# MCU_EM.net
KiCad netlist of a schematic drawn in Altium Designer
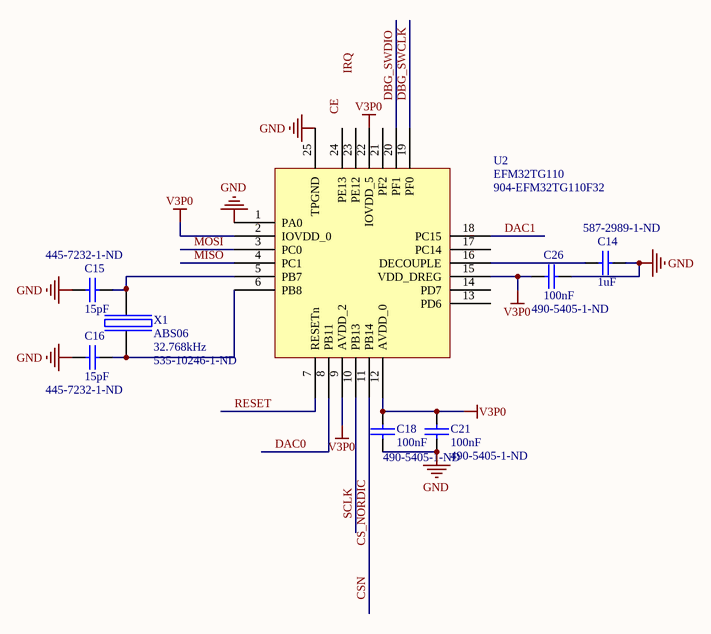
[diagram p0: MCU_EM.SchDoc]

(export (version "E")
  (design (tool "Eeschema 10.0.6"))
  (components
    (comp (ref "C14")
      (value "1uF")
      (footprint "0402s")
      (description "Capacitor")
      (fields
        (field (name "SUPPLIER PART NUMBER 1") "587-2989-1-ND")
        (field (name "MANUFACTURER") "Taiyo Yuden")
        (field (name "MANUFACTURER PART NUMBER") "AMK063ABJ105MP-F")
      )
      (libsource (lib "nRF24LE1F16Q24") (part "Cap"))
    )
    (comp (ref "C15")
      (value "15pF")
      (footprint "0201")
      (description "Capacitor")
      (fields
        (field (name "SUPPLIER PART NUMBER 1") "445-7232-1-ND")
        (field (name "MANUFACTURER") "TDK Corporation")
        (field (name "MANUFACTURER PART NUMBER") "C0603C0G1E150G")
      )
      (libsource (lib "nRF24LE1F16Q24") (part "Cap"))
    )
    (comp (ref "C16")
      (value "15pF")
      (footprint "0201")
      (description "Capacitor")
      (fields
        (field (name "SUPPLIER PART NUMBER 1") "445-7232-1-ND")
        (field (name "MANUFACTURER") "TDK Corporation")
        (field (name "MANUFACTURER PART NUMBER") "C0603C0G1E150G")
      )
      (libsource (lib "nRF24LE1F16Q24") (part "Cap"))
    )
    (comp (ref "C18")
      (value "100nF")
      (footprint "0201")
      (description "Capacitor")
      (fields
        (field (name "SUPPLIER PART NUMBER 1") "490-5405-1-ND")
        (field (name "MANUFACTURER") "Murata Electronics North America")
        (field (name "MANUFACTURER PART NUMBER") "GRM033R61A104ME15D")
      )
      (libsource (lib "nRF24LE1F16Q24") (part "Cap"))
    )
    (comp (ref "C21")
      (value "100nF")
      (footprint "0201")
      (description "Capacitor")
      (fields
        (field (name "SUPPLIER PART NUMBER 1") "490-5405-1-ND")
        (field (name "MANUFACTURER") "Murata Electronics North America")
        (field (name "MANUFACTURER PART NUMBER") "GRM033R61A104ME15D")
      )
      (libsource (lib "nRF24LE1F16Q24") (part "Cap"))
    )
    (comp (ref "C26")
      (value "100nF")
      (footprint "0402s")
      (description "Capacitor")
      (fields
        (field (name "SUPPLIER PART NUMBER 1") "490-5405-1-ND")
        (field (name "MANUFACTURER") "Murata Electronics North America")
        (field (name "MANUFACTURER PART NUMBER") "GRM033R61A104ME15D")
      )
      (libsource (lib "nRF24LE1F16Q24") (part "Cap"))
    )
    (comp (ref "U2")
      (value "EFM32TG110")
      (footprint "QFN24_EM")
      (description "Microcontrollers (MCU) 32KB Flash 4KB RAM")
      (fields
        (field (name "MANUFACTURER") "Energy Micro")
        (field (name "SUPPLIER PART NUMBER 1") "904-EFM32TG110F32")
      )
      (libsource (lib "custom") (part "EFM32TG110"))
    )
    (comp (ref "X1")
      (value "ABS06")
      (footprint "ABS06")
      (description "CRYSTAL 32.768 KHZ 9.0 PF SMD")
      (fields
        (field (name "MANUFACTURER") "Abracon Corporation")
        (field (name "MANUFACTURER PART NUMBER") "ABS06-32.768KHZ-9-T")
        (field (name "FREQUENCY") "32.768kHz")
        (field (name "SUPPLIER PART NUMBER 1") "535-10246-1-ND")
      )
      (libsource (lib "custom") (part "ABS06"))
    )
  )
  (nets
    (net (code "2") (name "/CSN") (class "Default")
      (node (ref "U2") (pin "11") (pinfunction "PB14_11") (pintype "passive"))
    )
    (net (code "3") (name "/DAC0") (class "Default")
      (node (ref "U2") (pin "8") (pinfunction "PB11_8") (pintype "passive"))
    )
    (net (code "4") (name "/DAC1") (class "Default")
      (node (ref "U2") (pin "18") (pinfunction "PC15_18") (pintype "passive"))
    )
    (net (code "5") (name "/DBG_SWCLK") (class "Default")
      (node (ref "U2") (pin "19") (pinfunction "PF0_19") (pintype "passive"))
    )
    (net (code "6") (name "/DBG_SWDIO") (class "Default")
      (node (ref "U2") (pin "20") (pinfunction "PF1_20") (pintype "passive"))
    )
    (net (code "8") (name "/MISO") (class "Default")
      (node (ref "U2") (pin "4") (pinfunction "PC1_4") (pintype "passive"))
    )
    (net (code "9") (name "/MOSI") (class "Default")
      (node (ref "U2") (pin "3") (pinfunction "PC0_3") (pintype "passive"))
    )
    (net (code "10") (name "/RESET") (class "Default")
      (node (ref "U2") (pin "7") (pinfunction "RESETn_7") (pintype "passive"))
    )
    (net (code "11") (name "/SCLK") (class "Default")
      (node (ref "U2") (pin "10") (pinfunction "PB13_10") (pintype "passive"))
    )
    (net (code "12") (name "GND") (class "Default")
      (node (ref "C14") (pin "1") (pintype "passive"))
      (node (ref "C15") (pin "1") (pintype "passive"))
      (node (ref "C16") (pin "2") (pintype "passive"))
      (node (ref "C18") (pin "2") (pintype "passive"))
      (node (ref "C21") (pin "2") (pintype "passive"))
      (node (ref "C26") (pin "2") (pintype "passive"))
      (node (ref "U2") (pin "1") (pinfunction "PA0_1") (pintype "passive"))
      (node (ref "U2") (pin "25") (pinfunction "TPGND_25") (pintype "passive"))
    )
    (net (code "13") (name "Net-(U2-DECOUPLE)") (class "Default")
      (node (ref "C14") (pin "2") (pintype "passive"))
      (node (ref "U2") (pin "16") (pinfunction "DECOUPLE_16") (pintype "passive"))
    )
    (net (code "14") (name "Net-(U2-PB7)") (class "Default")
      (node (ref "C15") (pin "2") (pintype "passive"))
      (node (ref "U2") (pin "5") (pinfunction "PB7_5") (pintype "passive"))
      (node (ref "X1") (pin "1") (pinfunction "inp_1") (pintype "passive"))
    )
    (net (code "15") (name "Net-(U2-PB8)") (class "Default")
      (node (ref "C16") (pin "1") (pintype "passive"))
      (node (ref "U2") (pin "6") (pinfunction "PB8_6") (pintype "passive"))
      (node (ref "X1") (pin "2") (pinfunction "out_2") (pintype "passive"))
    )
    (net (code "16") (name "V3P0") (class "Default")
      (node (ref "C18") (pin "1") (pintype "passive"))
      (node (ref "C21") (pin "1") (pintype "passive"))
      (node (ref "C26") (pin "1") (pintype "passive"))
      (node (ref "U2") (pin "12") (pinfunction "AVDD_0_12") (pintype "passive"))
      (node (ref "U2") (pin "15") (pinfunction "VDD_DREG_15") (pintype "passive"))
      (node (ref "U2") (pin "2") (pinfunction "IOVDD_0_2") (pintype "passive"))
      (node (ref "U2") (pin "22") (pinfunction "IOVDD_5_22") (pintype "passive"))
      (node (ref "U2") (pin "9") (pinfunction "AVDD_2_9") (pintype "passive"))
    )
    (net (code "17") (name "unconnected-(U2-PC14-Pad17)") (class "Default")
      (node (ref "U2") (pin "17") (pinfunction "PC14_17") (pintype "passive"))
    )
    (net (code "18") (name "unconnected-(U2-PD6-Pad13)") (class "Default")
      (node (ref "U2") (pin "13") (pinfunction "PD6_13") (pintype "passive"))
    )
    (net (code "19") (name "unconnected-(U2-PD7-Pad14)") (class "Default")
      (node (ref "U2") (pin "14") (pinfunction "PD7_14") (pintype "passive"))
    )
    (net (code "20") (name "unconnected-(U2-PE12-Pad23)") (class "Default")
      (node (ref "U2") (pin "23") (pinfunction "PE12_23") (pintype "passive"))
    )
    (net (code "21") (name "unconnected-(U2-PE13-Pad24)") (class "Default")
      (node (ref "U2") (pin "24") (pinfunction "PE13_24") (pintype "passive"))
    )
    (net (code "22") (name "unconnected-(U2-PF2-Pad21)") (class "Default")
      (node (ref "U2") (pin "21") (pinfunction "PF2_21") (pintype "passive"))
    )
  )
)
